# Schematic.net
KiCad netlist of a schematic drawn in EAGLE
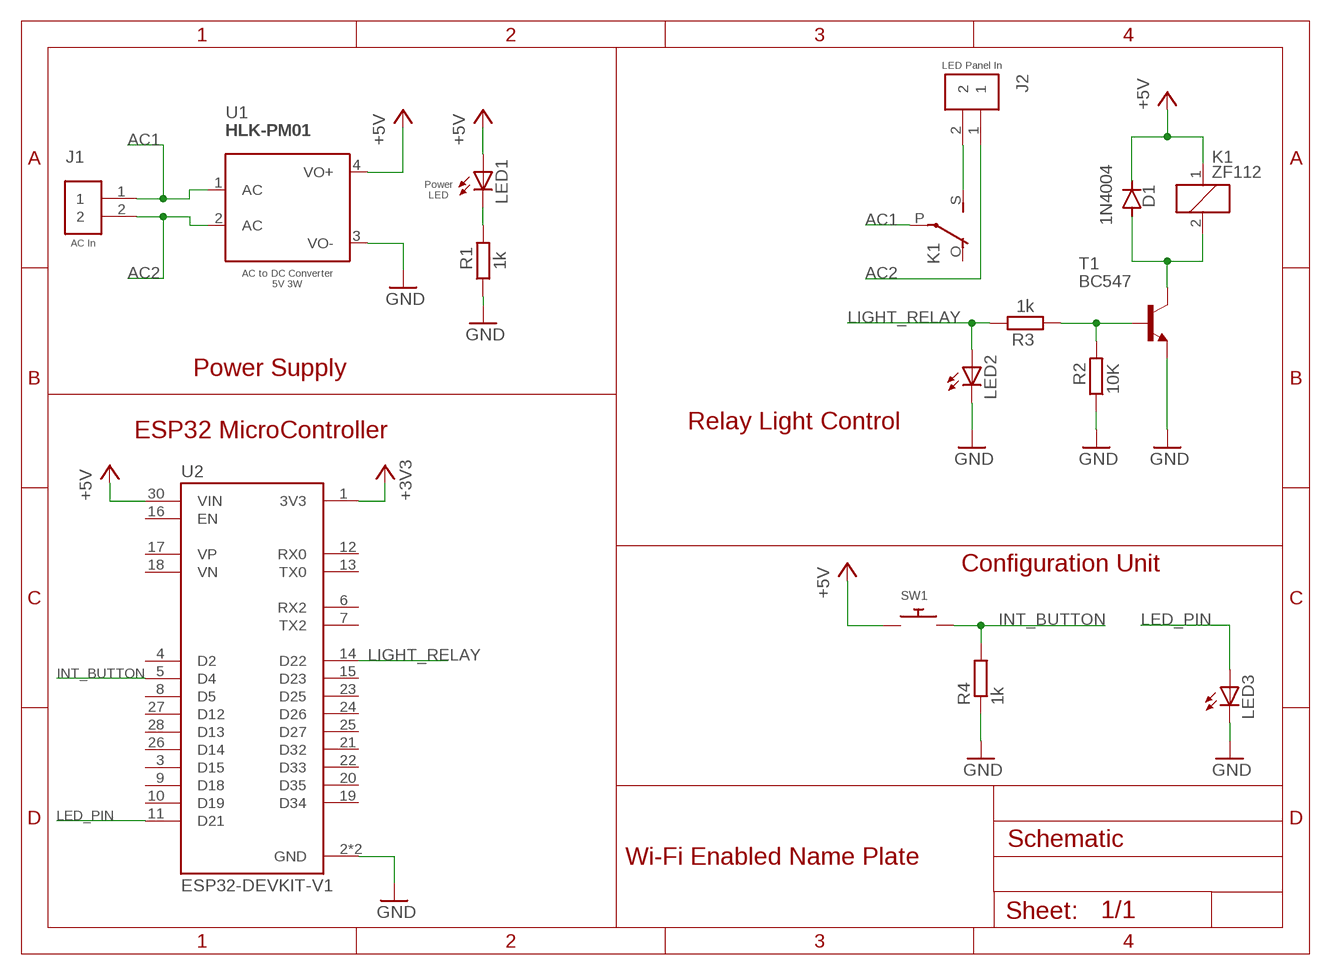
[diagram p0: schematic, sheet 1]

(export (version "E")
  (design (tool "Eeschema 10.0.6"))
  (components
    (comp (ref "D1")
      (value "1N4004")
      (footprint "eagle-import:DO41-10")
      (libsource (lib "eagle-import") (part "1N4004"))
    )
    (comp (ref "J1")
      (value "691311400102")
      (footprint "eagle-import:TERMINALBLOCK_PLUGGABLE-2-7.62MM")
      (fields
        (field (name "DIGIKEY_PART_NO") "732-2823-ND")
        (field (name "MANUFACTURER") "WURTH ELEKTRONIK")
        (field (name "CREATED_BY") "PCBLayout.com")
      )
      (libsource (lib "eagle-import") (part "691311400102"))
    )
    (comp (ref "J2")
      (value "691311400102")
      (footprint "eagle-import:TERMINALBLOCK_PLUGGABLE-2-7.62MM")
      (fields
        (field (name "DIGIKEY_PART_NO") "732-2823-ND")
        (field (name "MANUFACTURER") "WURTH ELEKTRONIK")
        (field (name "CREATED_BY") "PCBLayout.com")
      )
      (libsource (lib "eagle-import") (part "691311400102"))
    )
    (comp (ref "K1")
      (value "ZF112")
      (footprint "eagle-import:ZF112")
      (libsource (lib "eagle-import") (part "ZF112"))
    )
    (comp (ref "LED1")
      (value "LED3MM")
      (footprint "eagle-import:LED3MM")
      (libsource (lib "eagle-import") (part "LED3MM"))
    )
    (comp (ref "LED2")
      (value "LED3MM")
      (footprint "eagle-import:LED3MM")
      (libsource (lib "eagle-import") (part "LED3MM"))
    )
    (comp (ref "LED3")
      (value "LED3MM")
      (footprint "eagle-import:LED3MM")
      (libsource (lib "eagle-import") (part "LED3MM"))
    )
    (comp (ref "R1")
      (value "1k")
      (footprint "eagle-import:0204_7")
      (libsource (lib "eagle-import") (part "R-EU_0204/7"))
    )
    (comp (ref "R2")
      (value "10K")
      (footprint "eagle-import:0204_7")
      (libsource (lib "eagle-import") (part "R-EU_0204/7"))
    )
    (comp (ref "R3")
      (value "1k")
      (footprint "eagle-import:0204_7")
      (libsource (lib "eagle-import") (part "R-EU_0204/7"))
    )
    (comp (ref "R4")
      (value "1k")
      (footprint "eagle-import:0204_7")
      (libsource (lib "eagle-import") (part "R-EU_0204/7"))
    )
    (comp (ref "SW1")
      (value "SWITCH_PUSHBUTTONEVQ-PE")
      (footprint "eagle-import:TACT_PANA-EVQ")
      (libsource (lib "eagle-import") (part "SWITCH_PUSHBUTTONEVQ-PE"))
    )
    (comp (ref "T1")
      (value "BC547")
      (footprint "eagle-import:TO92")
      (libsource (lib "eagle-import") (part "BC547"))
    )
    (comp (ref "U1")
      (value "HLK-PM01")
      (footprint "eagle-import:HLK-PM01")
      (fields (field (name "MF") "Hi-link") (field (name "MP") "hlk-pm01"))
      (libsource (lib "eagle-import") (part "HLK-PM01"))
    )
    (comp (ref "U2")
      (value "ESP32-DEVKIT-V1")
      (footprint "eagle-import:MODULE_ESP32_DEVKIT_V1")
      (fields (field (name "MF") "Do it"))
      (libsource (lib "eagle-import") (part "ESP32-DEVKIT-V1"))
    )
  )
  (nets
    (net (code "1") (name "+3V3") (class "Default")
      (node (ref "U2") (pin "1") (pinfunction "3V3_1") (pintype "output"))
    )
    (net (code "2") (name "+5V") (class "Default")
      (node (ref "D1") (pin "C") (pinfunction "C_C") (pintype "passive"))
      (node (ref "K1") (pin "1") (pinfunction "1_1") (pintype "passive"))
      (node (ref "LED1") (pin "A") (pinfunction "A_A") (pintype "passive"))
      (node (ref "SW1") (pin "P$1") (pinfunction "P$1_P$1") (pintype "passive"))
      (node (ref "U1") (pin "4") (pinfunction "VO+_4") (pintype "bidirectional"))
      (node (ref "U2") (pin "30") (pinfunction "VIN_30") (pintype "input"))
    )
    (net (code "3") (name "/AC1") (class "Default")
      (node (ref "J1") (pin "1") (pinfunction "1_1") (pintype "passive"))
      (node (ref "K1") (pin "P") (pinfunction "P_P") (pintype "passive"))
      (node (ref "U1") (pin "1") (pinfunction "AC_1") (pintype "bidirectional"))
    )
    (net (code "4") (name "/AC2") (class "Default")
      (node (ref "J1") (pin "2") (pinfunction "2_2") (pintype "passive"))
      (node (ref "J2") (pin "1") (pinfunction "1_1") (pintype "passive"))
      (node (ref "U1") (pin "2") (pinfunction "AC_2") (pintype "bidirectional"))
    )
    (net (code "5") (name "/INT_BUTTON") (class "Default")
      (node (ref "R4") (pin "2") (pinfunction "2_2") (pintype "passive"))
      (node (ref "SW1") (pin "P$2") (pinfunction "P$2_P$2") (pintype "passive"))
      (node (ref "U2") (pin "5") (pinfunction "D4_5") (pintype "bidirectional"))
    )
    (net (code "6") (name "/LED_PIN") (class "Default")
      (node (ref "LED3") (pin "A") (pinfunction "A_A") (pintype "passive"))
      (node (ref "U2") (pin "11") (pinfunction "D21_11") (pintype "bidirectional"))
    )
    (net (code "7") (name "/LIGHT_RELAY") (class "Default")
      (node (ref "LED2") (pin "A") (pinfunction "A_A") (pintype "passive"))
      (node (ref "R3") (pin "2") (pinfunction "2_2") (pintype "passive"))
      (node (ref "U2") (pin "14") (pinfunction "D22_14") (pintype "bidirectional"))
    )
    (net (code "8") (name "GND") (class "Default")
      (node (ref "LED2") (pin "K") (pinfunction "C_K") (pintype "passive"))
      (node (ref "LED3") (pin "K") (pinfunction "C_K") (pintype "passive"))
      (node (ref "R1") (pin "1") (pinfunction "1_1") (pintype "passive"))
      (node (ref "R2") (pin "1") (pinfunction "1_1") (pintype "passive"))
      (node (ref "R4") (pin "1") (pinfunction "1_1") (pintype "passive"))
      (node (ref "T1") (pin "1") (pinfunction "E_1") (pintype "passive"))
      (node (ref "U1") (pin "3") (pinfunction "VO-_3") (pintype "bidirectional"))
      (node (ref "U2") (pin "2") (pinfunction "GND_2") (pintype "power_in"))
      (node (ref "U2") (pin "29") (pinfunction "GND_29") (pintype "power_in"))
    )
    (net (code "9") (name "Net-(J2-Pad2)") (class "Default")
      (node (ref "J2") (pin "2") (pinfunction "2_2") (pintype "passive"))
      (node (ref "K1") (pin "S") (pinfunction "S_S") (pintype "passive"))
    )
    (net (code "10") (name "Net-(LED1-C)") (class "Default")
      (node (ref "LED1") (pin "K") (pinfunction "C_K") (pintype "passive"))
      (node (ref "R1") (pin "2") (pinfunction "2_2") (pintype "passive"))
    )
    (net (code "11") (name "Net-(T1-B)") (class "Default")
      (node (ref "R2") (pin "2") (pinfunction "2_2") (pintype "passive"))
      (node (ref "R3") (pin "1") (pinfunction "1_1") (pintype "passive"))
      (node (ref "T1") (pin "2") (pinfunction "B_2") (pintype "passive"))
    )
    (net (code "12") (name "Net-(T1-C)") (class "Default")
      (node (ref "D1") (pin "A") (pinfunction "A_A") (pintype "passive"))
      (node (ref "K1") (pin "2") (pinfunction "2_2") (pintype "passive"))
      (node (ref "T1") (pin "3") (pinfunction "C_3") (pintype "passive"))
    )
    (net (code "13") (name "unconnected-(K1-PadO)") (class "Default")
      (node (ref "K1") (pin "O") (pinfunction "O_O") (pintype "passive"))
    )
    (net (code "14") (name "unconnected-(U2-D2-Pad4)") (class "Default")
      (node (ref "U2") (pin "4") (pinfunction "D2_4") (pintype "bidirectional"))
    )
    (net (code "15") (name "unconnected-(U2-D5-Pad8)") (class "Default")
      (node (ref "U2") (pin "8") (pinfunction "D5_8") (pintype "bidirectional"))
    )
    (net (code "16") (name "unconnected-(U2-D12-Pad27)") (class "Default")
      (node (ref "U2") (pin "27") (pinfunction "D12_27") (pintype "bidirectional"))
    )
    (net (code "17") (name "unconnected-(U2-D13-Pad28)") (class "Default")
      (node (ref "U2") (pin "28") (pinfunction "D13_28") (pintype "bidirectional"))
    )
    (net (code "18") (name "unconnected-(U2-D14-Pad26)") (class "Default")
      (node (ref "U2") (pin "26") (pinfunction "D14_26") (pintype "bidirectional"))
    )
    (net (code "19") (name "unconnected-(U2-D15-Pad3)") (class "Default")
      (node (ref "U2") (pin "3") (pinfunction "D15_3") (pintype "bidirectional"))
    )
    (net (code "20") (name "unconnected-(U2-D18-Pad9)") (class "Default")
      (node (ref "U2") (pin "9") (pinfunction "D18_9") (pintype "bidirectional"))
    )
    (net (code "21") (name "unconnected-(U2-D19-Pad10)") (class "Default")
      (node (ref "U2") (pin "10") (pinfunction "D19_10") (pintype "bidirectional"))
    )
    (net (code "22") (name "unconnected-(U2-D23-Pad15)") (class "Default")
      (node (ref "U2") (pin "15") (pinfunction "D23_15") (pintype "bidirectional"))
    )
    (net (code "23") (name "unconnected-(U2-D25-Pad23)") (class "Default")
      (node (ref "U2") (pin "23") (pinfunction "D25_23") (pintype "bidirectional"))
    )
    (net (code "24") (name "unconnected-(U2-D26-Pad24)") (class "Default")
      (node (ref "U2") (pin "24") (pinfunction "D26_24") (pintype "bidirectional"))
    )
    (net (code "25") (name "unconnected-(U2-D27-Pad25)") (class "Default")
      (node (ref "U2") (pin "25") (pinfunction "D27_25") (pintype "bidirectional"))
    )
    (net (code "26") (name "unconnected-(U2-D32-Pad21)") (class "Default")
      (node (ref "U2") (pin "21") (pinfunction "D32_21") (pintype "bidirectional"))
    )
    (net (code "27") (name "unconnected-(U2-D33-Pad22)") (class "Default")
      (node (ref "U2") (pin "22") (pinfunction "D33_22") (pintype "bidirectional"))
    )
    (net (code "28") (name "unconnected-(U2-D34-Pad19)") (class "Default")
      (node (ref "U2") (pin "19") (pinfunction "D34_19") (pintype "bidirectional"))
    )
    (net (code "29") (name "unconnected-(U2-D35-Pad20)") (class "Default")
      (node (ref "U2") (pin "20") (pinfunction "D35_20") (pintype "bidirectional"))
    )
    (net (code "30") (name "unconnected-(U2-EN-Pad16)") (class "Default")
      (node (ref "U2") (pin "16") (pinfunction "EN_16") (pintype "input"))
    )
    (net (code "31") (name "unconnected-(U2-RX0-Pad12)") (class "Default")
      (node (ref "U2") (pin "12") (pinfunction "RX0_12") (pintype "input"))
    )
    (net (code "32") (name "unconnected-(U2-RX2-Pad6)") (class "Default")
      (node (ref "U2") (pin "6") (pinfunction "RX2_6") (pintype "input"))
    )
    (net (code "33") (name "unconnected-(U2-TX0-Pad13)") (class "Default")
      (node (ref "U2") (pin "13") (pinfunction "TX0_13") (pintype "output"))
    )
    (net (code "34") (name "unconnected-(U2-TX2-Pad7)") (class "Default")
      (node (ref "U2") (pin "7") (pinfunction "TX2_7") (pintype "output"))
    )
    (net (code "35") (name "unconnected-(U2-VN-Pad18)") (class "Default")
      (node (ref "U2") (pin "18") (pinfunction "VN_18") (pintype "bidirectional"))
    )
    (net (code "36") (name "unconnected-(U2-VP-Pad17)") (class "Default")
      (node (ref "U2") (pin "17") (pinfunction "VP_17") (pintype "bidirectional"))
    )
  )
)
